# PowerSysPractice.net
KiCad netlist of a schematic drawn in EAGLE
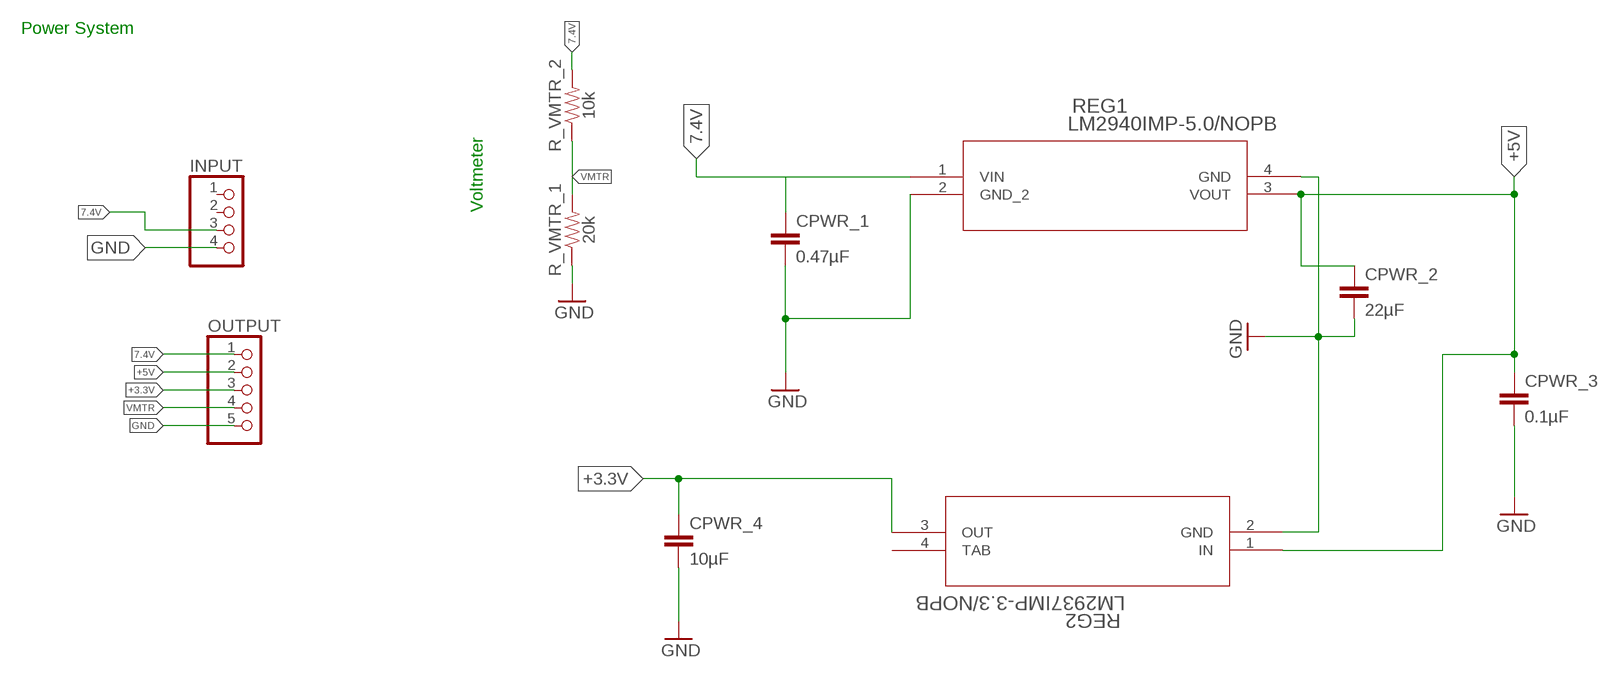
[diagram p0: schematic, sheet 1]

(export (version "E")
  (design (tool "Eeschema 10.0.6"))
  (components
    (comp (ref "CPWR_1")
      (value "0.47µF")
      (footprint "eagle-import:0805")
      (libsource (lib "eagle-import") (part "0.33UF/330NF-0805-50V-10%"))
    )
    (comp (ref "CPWR_2")
      (value "22µF")
      (footprint "eagle-import:0805")
      (libsource (lib "eagle-import") (part "0.33UF/330NF-0805-50V-10%"))
    )
    (comp (ref "CPWR_3")
      (value "0.1µF")
      (footprint "eagle-import:0805")
      (libsource (lib "eagle-import") (part "0.33UF/330NF-0805-50V-10%"))
    )
    (comp (ref "CPWR_4")
      (value "10µF")
      (footprint "eagle-import:0805")
      (libsource (lib "eagle-import") (part "0.33UF/330NF-0805-50V-10%"))
    )
    (comp (ref "INPUT")
      (value "PINHD-1X4")
      (footprint "eagle-import:1X04")
      (libsource (lib "eagle-import") (part "PINHD-1X4"))
    )
    (comp (ref "OUTPUT")
      (value "PINHD-1X5")
      (footprint "eagle-import:1X05")
      (libsource (lib "eagle-import") (part "PINHD-1X5"))
    )
    (comp (ref "REG1")
      (value "LM2940IMP-5.0/NOPB")
      (footprint "eagle-import:MP04A")
      (fields
        (field (name "MANUFACTURER_PART_NUMBER") "LM2940IMP5.0NOPB")
        (field (name "COPYRIGHT") "Copyright C 2015 Accelerated Designs. All rights reserved")
      )
      (libsource (lib "eagle-import") (part "LM2940IMP-5.0/NOPB"))
    )
    (comp (ref "REG2")
      (value "LM2937IMP-3.3/NOPB")
      (footprint "eagle-import:MP04A")
      (fields
        (field (name "MANUFACTURER_PART_NUMBER") "lm2937imp3_3nopb")
        (field (name "COPYRIGHT") "Copyright C 2015 Accelerated Designs. All rights reserved")
      )
      (libsource (lib "eagle-import") (part "LM2937IMP-3.3/NOPB"))
    )
    (comp (ref "R_VMTR_1")
      (value "20k")
      (footprint "eagle-import:0805")
      (libsource (lib "eagle-import") (part "0.75OHM-0805-1/4W-1%"))
    )
    (comp (ref "R_VMTR_2")
      (value "10k")
      (footprint "eagle-import:0805")
      (libsource (lib "eagle-import") (part "0.75OHM-0805-1/4W-1%"))
    )
  )
  (nets
    (net (code "1") (name "+3.3V") (class "Default")
      (node (ref "CPWR_4") (pin "1") (pinfunction "1_1") (pintype "passive"))
      (node (ref "OUTPUT") (pin "3") (pinfunction "3_3") (pintype "passive"))
      (node (ref "REG2") (pin "3") (pinfunction "OUT_3") (pintype "power_in"))
    )
    (net (code "2") (name "+5V") (class "Default")
      (node (ref "CPWR_2") (pin "1") (pinfunction "1_1") (pintype "passive"))
      (node (ref "CPWR_3") (pin "1") (pinfunction "1_1") (pintype "passive"))
      (node (ref "OUTPUT") (pin "2") (pinfunction "2_2") (pintype "passive"))
      (node (ref "REG1") (pin "3") (pinfunction "VOUT_3") (pintype "output"))
      (node (ref "REG2") (pin "1") (pinfunction "IN_1") (pintype "power_in"))
    )
    (net (code "3") (name "/TAB") (class "Default")
      (node (ref "REG2") (pin "4") (pinfunction "TAB_4") (pintype "power_in"))
    )
    (net (code "4") (name "7.4V") (class "Default")
      (node (ref "CPWR_1") (pin "1") (pinfunction "1_1") (pintype "passive"))
      (node (ref "INPUT") (pin "3") (pinfunction "3_3") (pintype "passive"))
      (node (ref "OUTPUT") (pin "1") (pinfunction "1_1") (pintype "passive"))
      (node (ref "REG1") (pin "1") (pinfunction "VIN_1") (pintype "input"))
      (node (ref "R_VMTR_2") (pin "2") (pinfunction "2_2") (pintype "passive"))
    )
    (net (code "5") (name "GND") (class "Default")
      (node (ref "CPWR_1") (pin "2") (pinfunction "2_2") (pintype "passive"))
      (node (ref "CPWR_2") (pin "2") (pinfunction "2_2") (pintype "passive"))
      (node (ref "CPWR_3") (pin "2") (pinfunction "2_2") (pintype "passive"))
      (node (ref "CPWR_4") (pin "2") (pinfunction "2_2") (pintype "passive"))
      (node (ref "INPUT") (pin "4") (pinfunction "4_4") (pintype "passive"))
      (node (ref "OUTPUT") (pin "5") (pinfunction "5_5") (pintype "passive"))
      (node (ref "REG1") (pin "2") (pinfunction "GND_2_2") (pintype "power_in"))
      (node (ref "REG1") (pin "4") (pinfunction "GND_4") (pintype "power_in"))
      (node (ref "REG2") (pin "2") (pinfunction "GND_2") (pintype "power_in"))
      (node (ref "R_VMTR_1") (pin "1") (pinfunction "1_1") (pintype "passive"))
    )
    (net (code "6") (name "VMTR") (class "Default")
      (node (ref "OUTPUT") (pin "4") (pinfunction "4_4") (pintype "passive"))
      (node (ref "R_VMTR_1") (pin "2") (pinfunction "2_2") (pintype "passive"))
      (node (ref "R_VMTR_2") (pin "1") (pinfunction "1_1") (pintype "passive"))
    )
    (net (code "7") (name "unconnected-(INPUT-Pad1)") (class "Default")
      (node (ref "INPUT") (pin "1") (pinfunction "1_1") (pintype "passive"))
    )
    (net (code "8") (name "unconnected-(INPUT-Pad2)") (class "Default")
      (node (ref "INPUT") (pin "2") (pinfunction "2_2") (pintype "passive"))
    )
  )
)
